# megacommand24.net
KiCad netlist of a schematic drawn in EAGLE
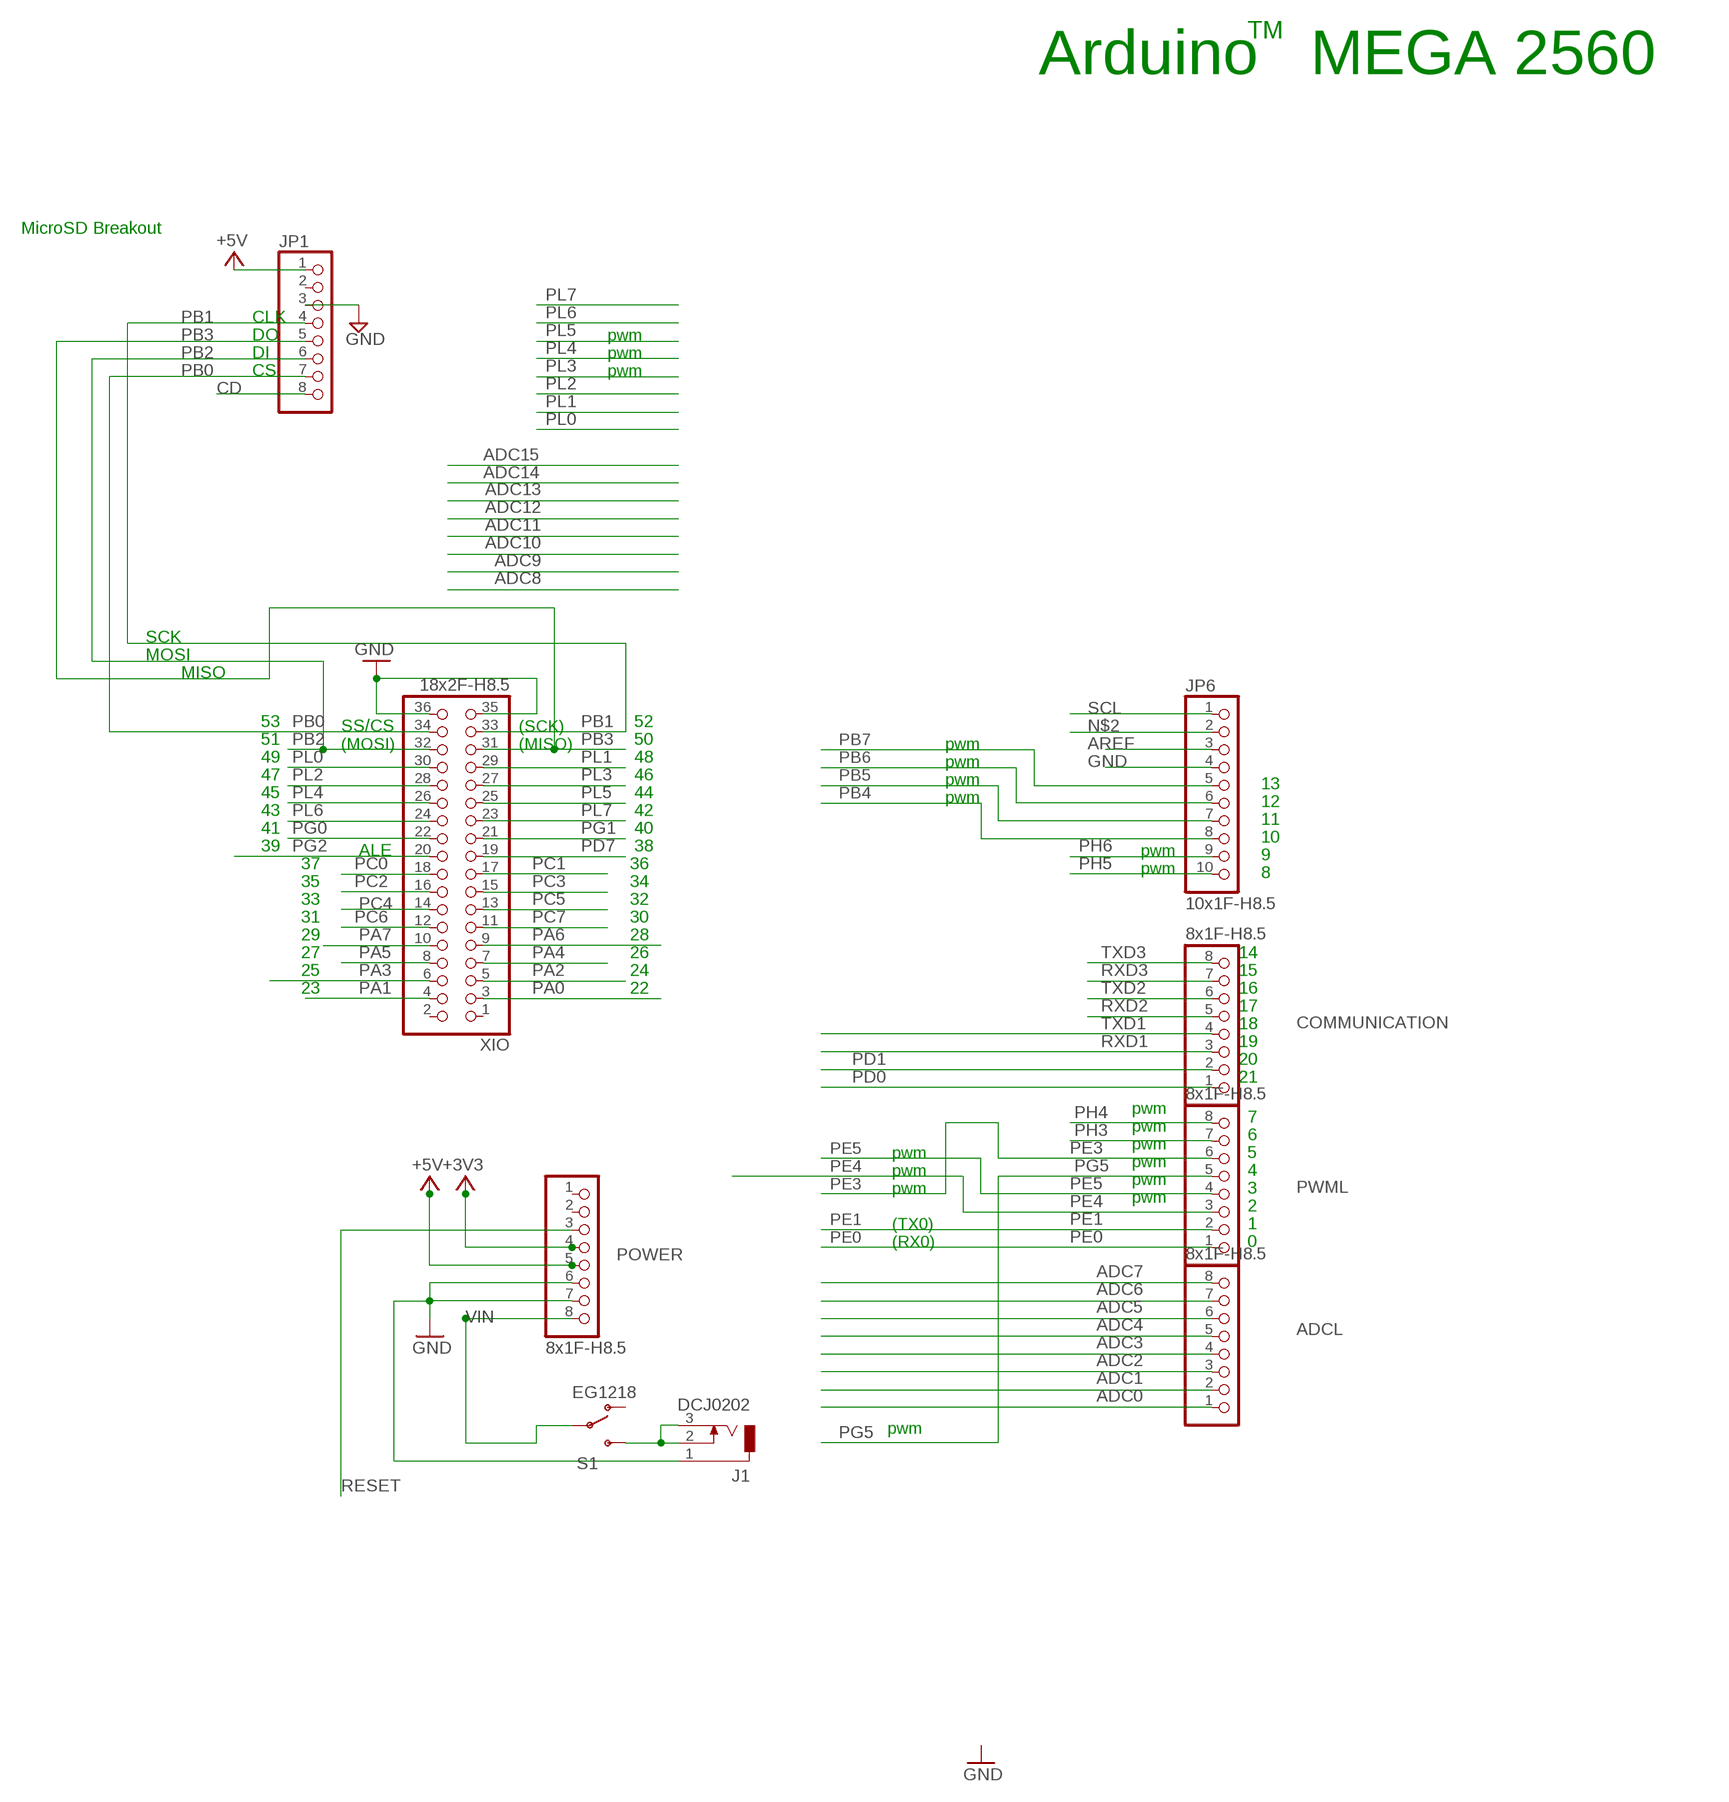
[diagram p0: schematic, sheet 1]
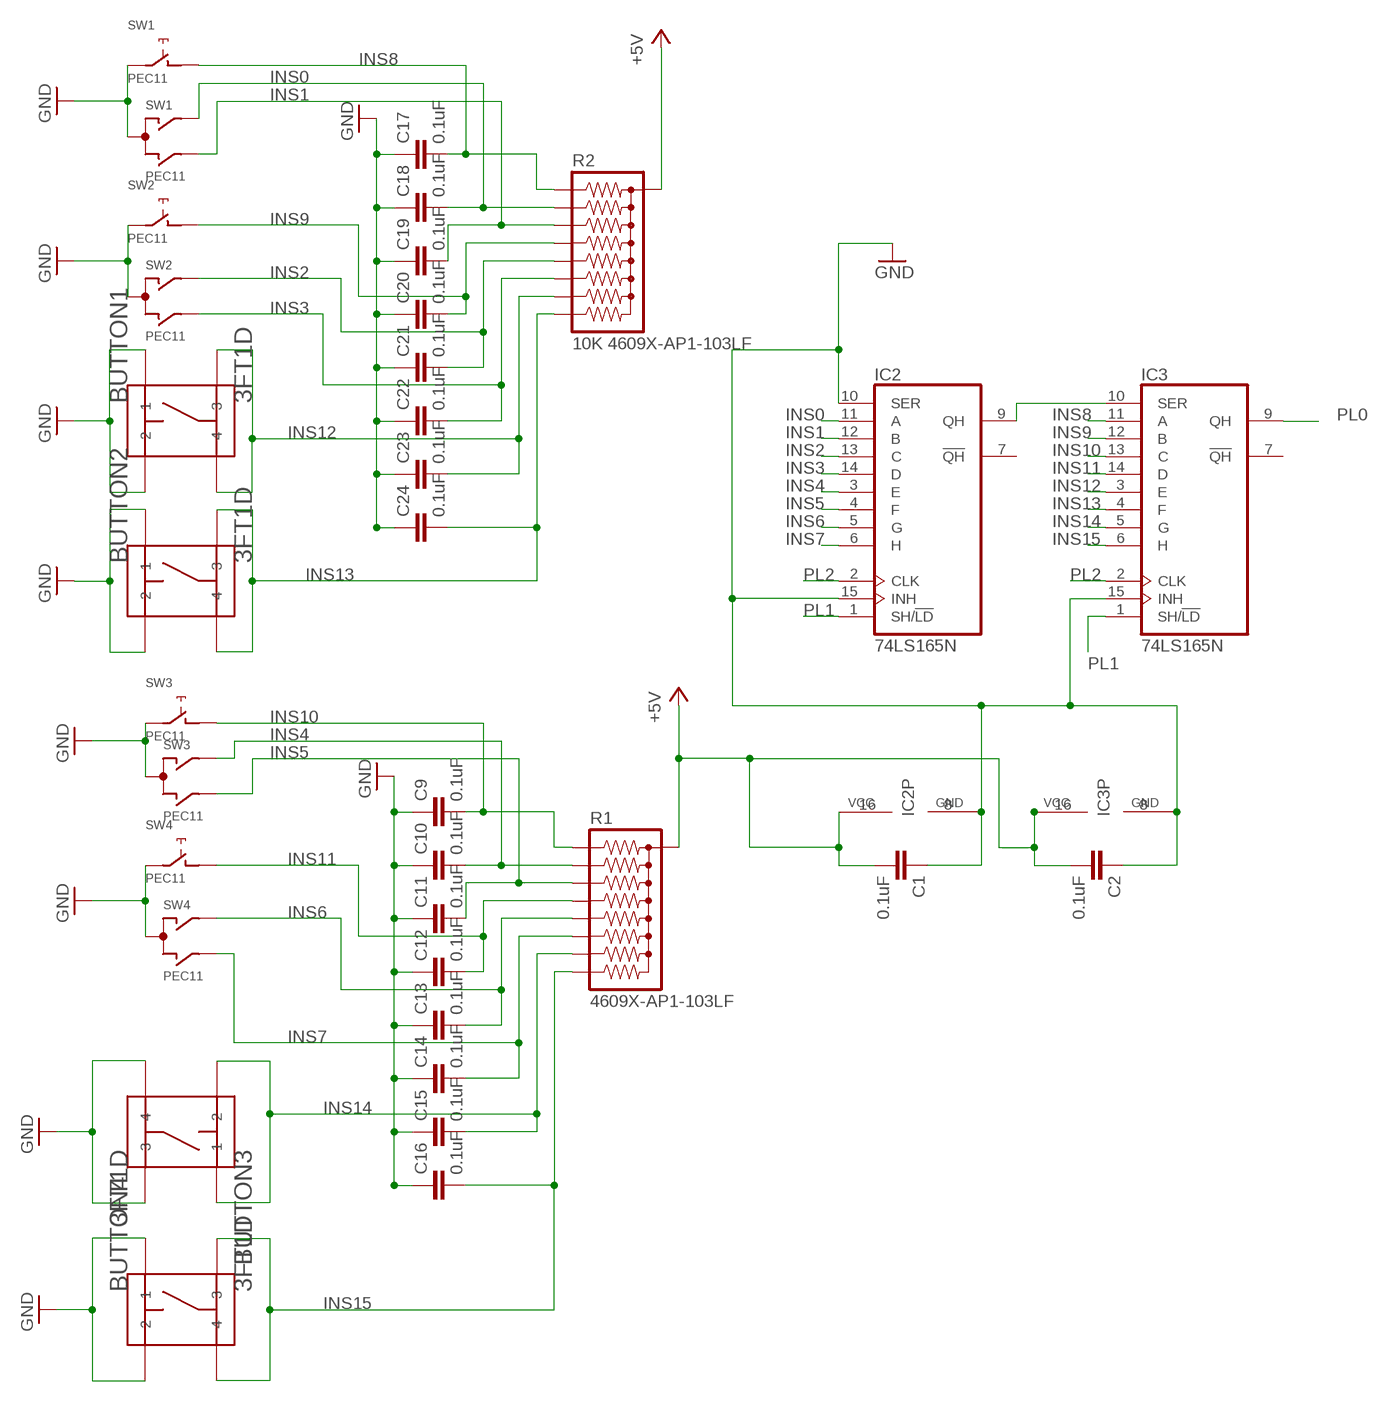
[diagram p1: schematic, sheet 2]
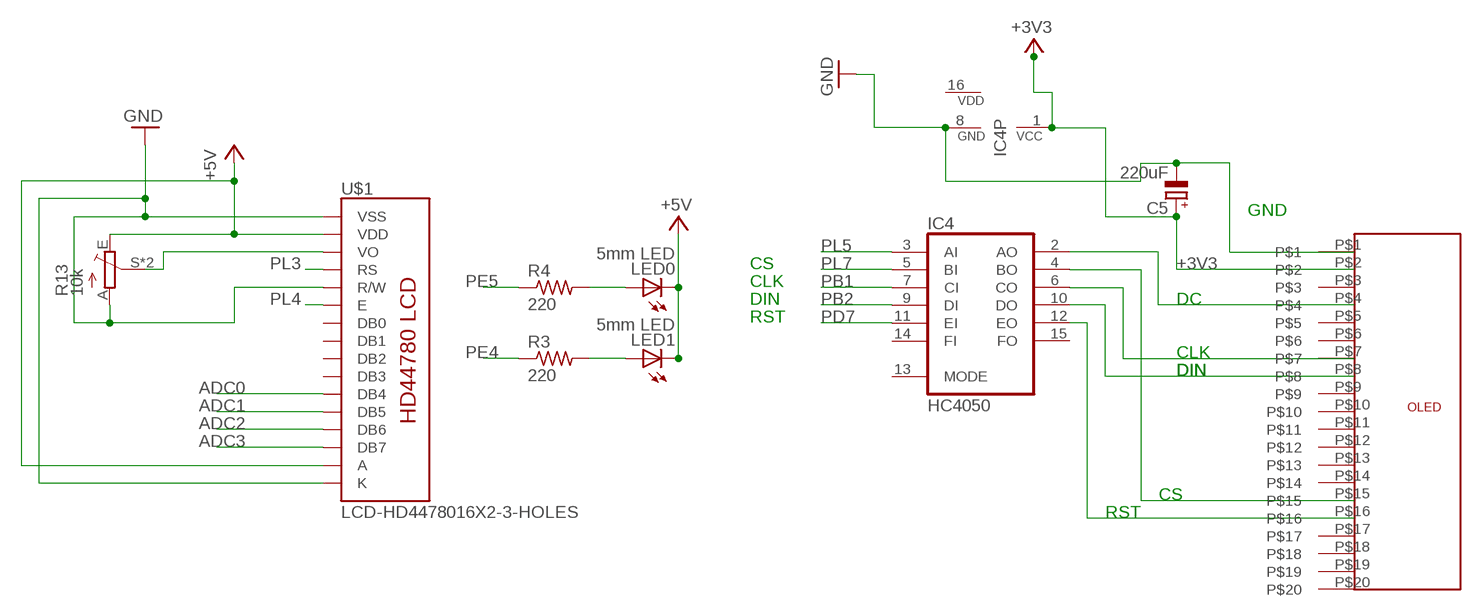
[diagram p2: schematic, sheet 3]
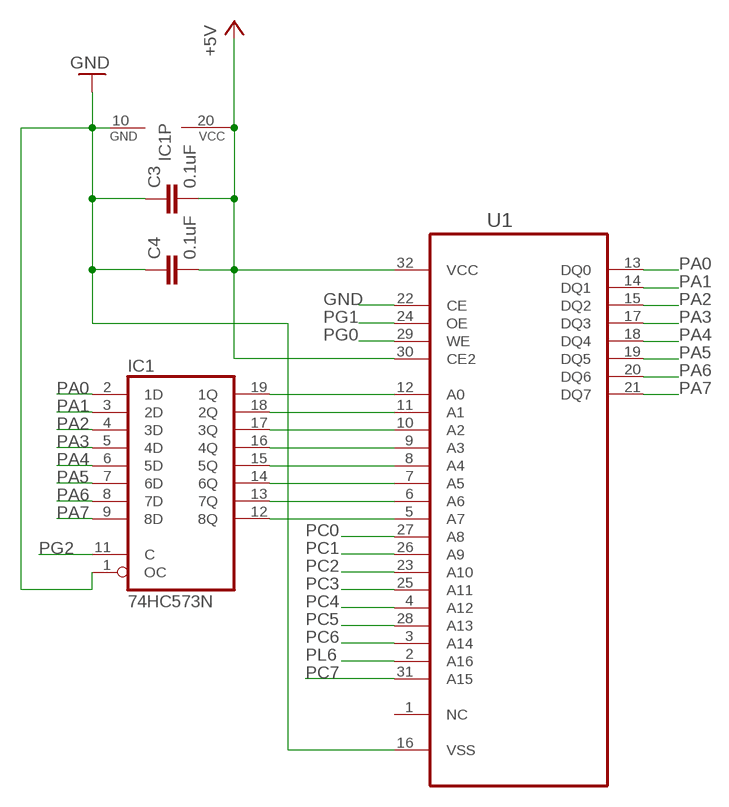
[diagram p3: schematic, sheet 4]
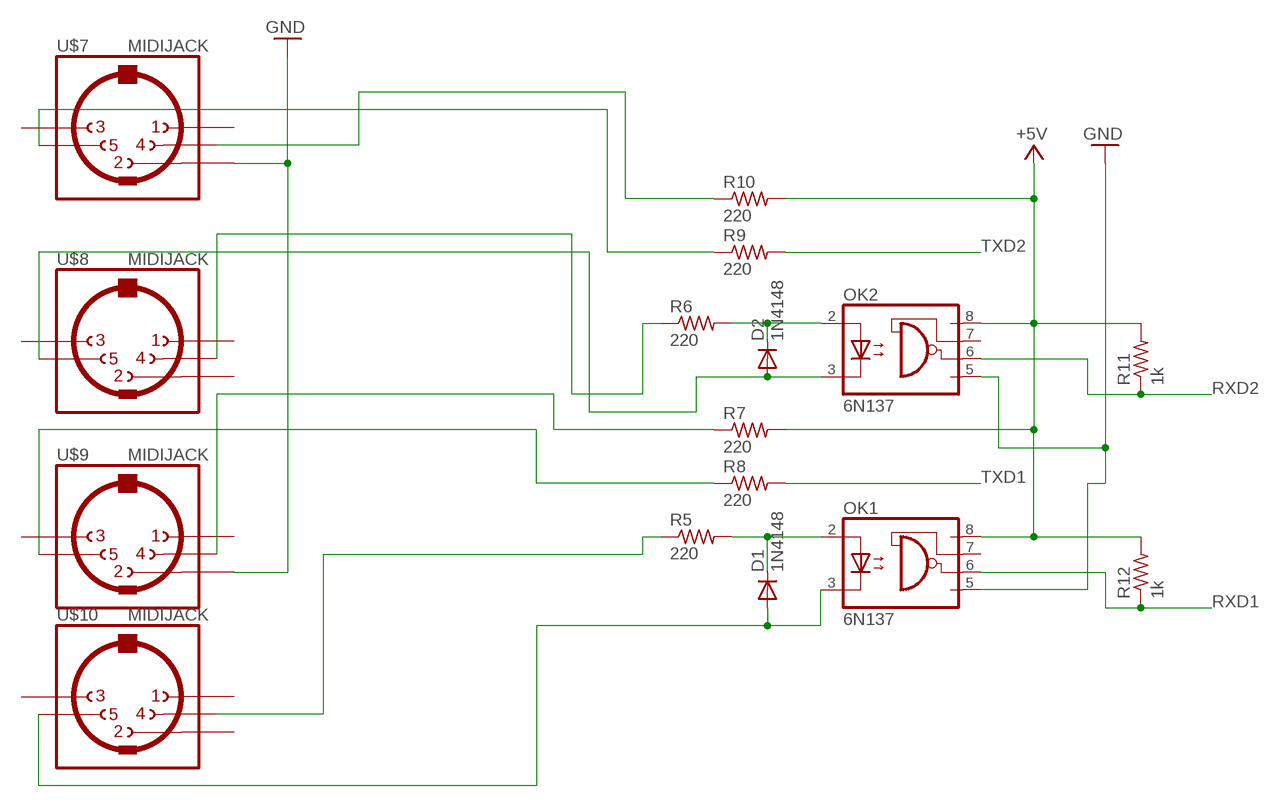
[diagram p4: schematic, sheet 5]

(export (version "E")
  (design (tool "Eeschema 10.0.6"))
  (components
    (comp (ref "ADCL")
      (value "8x1F-H8.5")
      (footprint "eagle-import:1X08")
      (libsource (lib "eagle-import") (part "PINHD-1X8"))
    )
    (comp (ref "COMMUNICATION")
      (value "8x1F-H8.5")
      (footprint "eagle-import:1X08")
      (libsource (lib "eagle-import") (part "PINHD-1X8"))
    )
    (comp (ref "J1")
      (value "DCJ0202")
      (footprint "eagle-import:DCJ0202")
      (libsource (lib "eagle-import") (part "DCJ0202"))
    )
    (comp (ref "JP1")
      (value "PINHD-1X8BIG")
      (footprint "eagle-import:1X08-BIG")
      (libsource (lib "eagle-import") (part "PINHD-1X8BIG"))
    )
    (comp (ref "JP6")
      (value "10x1F-H8.5")
      (footprint "eagle-import:1X10")
      (libsource (lib "eagle-import") (part "PINHD-1X10_ARD"))
    )
    (comp (ref "POWER")
      (value "8x1F-H8.5")
      (footprint "eagle-import:1X08")
      (libsource (lib "eagle-import") (part "PINHD-1X8"))
    )
    (comp (ref "PWML")
      (value "8x1F-H8.5")
      (footprint "eagle-import:1X08")
      (libsource (lib "eagle-import") (part "PINHD-1X8"))
    )
    (comp (ref "S1")
      (value "EG1218")
      (footprint "eagle-import:SWITCH-SPDT_KIT")
      (libsource (lib "eagle-import") (part "SWITCH-SPDTKIT"))
    )
    (comp (ref "XIO")
      (value "18x2F-H8.5")
      (footprint "eagle-import:2X18")
      (libsource (lib "eagle-import") (part "PINHD-2X18"))
    )
    (comp (ref "D1")
      (value "1N4148")
      (footprint "eagle-import:DO35-7")
      (libsource (lib "eagle-import") (part "1N4148DO35-7"))
    )
    (comp (ref "D2")
      (value "1N4148")
      (footprint "eagle-import:DO35-7")
      (libsource (lib "eagle-import") (part "1N4148DO35-7"))
    )
    (comp (ref "OK1")
      (value "6N137")
      (footprint "eagle-import:DIL08")
      (libsource (lib "eagle-import") (part "6N137"))
    )
    (comp (ref "OK2")
      (value "6N137")
      (footprint "eagle-import:DIL08")
      (libsource (lib "eagle-import") (part "6N137"))
    )
    (comp (ref "R5")
      (value "220")
      (footprint "eagle-import:0207_7")
      (libsource (lib "eagle-import") (part "R-US_0207/7"))
    )
    (comp (ref "R6")
      (value "220")
      (footprint "eagle-import:0207_7")
      (libsource (lib "eagle-import") (part "R-US_0207/7"))
    )
    (comp (ref "R7")
      (value "220")
      (footprint "eagle-import:0207_7")
      (libsource (lib "eagle-import") (part "R-US_0207/7"))
    )
    (comp (ref "R8")
      (value "220")
      (footprint "eagle-import:0207_7")
      (libsource (lib "eagle-import") (part "R-US_0207/7"))
    )
    (comp (ref "R9")
      (value "220")
      (footprint "eagle-import:0207_7")
      (libsource (lib "eagle-import") (part "R-US_0207/7"))
    )
    (comp (ref "R10")
      (value "220")
      (footprint "eagle-import:0207_7")
      (libsource (lib "eagle-import") (part "R-US_0207/7"))
    )
    (comp (ref "R11")
      (value "1k")
      (footprint "eagle-import:0207_7")
      (libsource (lib "eagle-import") (part "R-US_0207/7"))
    )
    (comp (ref "R12")
      (value "1k")
      (footprint "eagle-import:0207_7")
      (libsource (lib "eagle-import") (part "R-US_0207/7"))
    )
    (comp (ref "U$7")
      (value "MIDIJACK")
      (footprint "eagle-import:CP-2350")
      (libsource (lib "eagle-import") (part "MIDIJACK"))
    )
    (comp (ref "U$8")
      (value "MIDIJACK")
      (footprint "eagle-import:CP-2350")
      (libsource (lib "eagle-import") (part "MIDIJACK"))
    )
    (comp (ref "U$9")
      (value "MIDIJACK")
      (footprint "eagle-import:CP-2350")
      (libsource (lib "eagle-import") (part "MIDIJACK"))
    )
    (comp (ref "U$10")
      (value "MIDIJACK")
      (footprint "eagle-import:CP-2350")
      (libsource (lib "eagle-import") (part "MIDIJACK"))
    )
    (comp (ref "C5")
      (value "220uF")
      (footprint "eagle-import:TT2D6")
      (libsource (lib "eagle-import") (part "CPOL-EUTT2D6"))
    )
    (comp (ref "IC4")
      (value "HC4050")
      (footprint "eagle-import:DIL16")
      (libsource (lib "eagle-import") (part "4504N"))
    )
    (comp (ref "LED0")
      (value "5mm LED")
      (footprint "eagle-import:LED_LD260")
      (libsource (lib "eagle-import") (part "LED_ELD260"))
    )
    (comp (ref "LED1")
      (value "5mm LED")
      (footprint "eagle-import:LED_LD260")
      (libsource (lib "eagle-import") (part "LED_ELD260"))
    )
    (comp (ref "R3")
      (value "220")
      (footprint "eagle-import:0207_7")
      (libsource (lib "eagle-import") (part "R-US_0207/7"))
    )
    (comp (ref "R4")
      (value "220")
      (footprint "eagle-import:0207_7")
      (libsource (lib "eagle-import") (part "R-US_0207/7"))
    )
    (comp (ref "R13")
      (value "10k")
      (footprint "eagle-import:CA6V")
      (libsource (lib "eagle-import") (part "TRIM_EU-CA6V"))
    )
    (comp (ref "U$1")
      (value "LCD-HD4478016X2-3-HOLES")
      (footprint "eagle-import:LCD-16X2-3HOLES")
      (libsource (lib "eagle-import") (part "LCD-HD4478016X2-3-HOLES"))
    )
    (comp (ref "U$2")
      (value "20PIN")
      (footprint "eagle-import:20PIN")
      (libsource (lib "eagle-import") (part "20PIN"))
    )
    (comp (ref "BUTTON1")
      (value "3FT1D")
      (footprint "eagle-import:3FT")
      (libsource (lib "eagle-import") (part "3FT1D"))
    )
    (comp (ref "BUTTON2")
      (value "3FT1D")
      (footprint "eagle-import:3FT")
      (libsource (lib "eagle-import") (part "3FT1D"))
    )
    (comp (ref "BUTTON3")
      (value "3FT1D")
      (footprint "eagle-import:3FT")
      (libsource (lib "eagle-import") (part "3FT1D"))
    )
    (comp (ref "BUTTON4")
      (value "3FT1D")
      (footprint "eagle-import:3FT")
      (libsource (lib "eagle-import") (part "3FT1D"))
    )
    (comp (ref "C1")
      (value "0.1uF")
      (footprint "eagle-import:C025-050X050")
      (libsource (lib "eagle-import") (part "C-EU025-050X050"))
    )
    (comp (ref "C2")
      (value "0.1uF")
      (footprint "eagle-import:C025-050X050")
      (libsource (lib "eagle-import") (part "C-EU025-050X050"))
    )
    (comp (ref "C9")
      (value "0.1uF")
      (footprint "eagle-import:C025-050X050")
      (libsource (lib "eagle-import") (part "C-EU025-050X050"))
    )
    (comp (ref "C10")
      (value "0.1uF")
      (footprint "eagle-import:C025-050X050")
      (libsource (lib "eagle-import") (part "C-EU025-050X050"))
    )
    (comp (ref "C11")
      (value "0.1uF")
      (footprint "eagle-import:C025-050X050")
      (libsource (lib "eagle-import") (part "C-EU025-050X050"))
    )
    (comp (ref "C12")
      (value "0.1uF")
      (footprint "eagle-import:C025-050X050")
      (libsource (lib "eagle-import") (part "C-EU025-050X050"))
    )
    (comp (ref "C13")
      (value "0.1uF")
      (footprint "eagle-import:C025-050X050")
      (libsource (lib "eagle-import") (part "C-EU025-050X050"))
    )
    (comp (ref "C14")
      (value "0.1uF")
      (footprint "eagle-import:C025-050X050")
      (libsource (lib "eagle-import") (part "C-EU025-050X050"))
    )
    (comp (ref "C15")
      (value "0.1uF")
      (footprint "eagle-import:C025-050X050")
      (libsource (lib "eagle-import") (part "C-EU025-050X050"))
    )
    (comp (ref "C16")
      (value "0.1uF")
      (footprint "eagle-import:C025-050X050")
      (libsource (lib "eagle-import") (part "C-EU025-050X050"))
    )
    (comp (ref "C17")
      (value "0.1uF")
      (footprint "eagle-import:C025-050X050")
      (libsource (lib "eagle-import") (part "C-EU025-050X050"))
    )
    (comp (ref "C18")
      (value "0.1uF")
      (footprint "eagle-import:C025-050X050")
      (libsource (lib "eagle-import") (part "C-EU025-050X050"))
    )
    (comp (ref "C19")
      (value "0.1uF")
      (footprint "eagle-import:C025-050X050")
      (libsource (lib "eagle-import") (part "C-EU025-050X050"))
    )
    (comp (ref "C20")
      (value "0.1uF")
      (footprint "eagle-import:C025-050X050")
      (libsource (lib "eagle-import") (part "C-EU025-050X050"))
    )
    (comp (ref "C21")
      (value "0.1uF")
      (footprint "eagle-import:C025-050X050")
      (libsource (lib "eagle-import") (part "C-EU025-050X050"))
    )
    (comp (ref "C22")
      (value "0.1uF")
      (footprint "eagle-import:C025-050X050")
      (libsource (lib "eagle-import") (part "C-EU025-050X050"))
    )
    (comp (ref "C23")
      (value "0.1uF")
      (footprint "eagle-import:C025-050X050")
      (libsource (lib "eagle-import") (part "C-EU025-050X050"))
    )
    (comp (ref "C24")
      (value "0.1uF")
      (footprint "eagle-import:C025-050X050")
      (libsource (lib "eagle-import") (part "C-EU025-050X050"))
    )
    (comp (ref "IC2")
      (value "74LS165N")
      (footprint "eagle-import:DIL16")
      (libsource (lib "eagle-import") (part "74165NLS"))
    )
    (comp (ref "IC3")
      (value "74LS165N")
      (footprint "eagle-import:DIL16")
      (libsource (lib "eagle-import") (part "74165NLS"))
    )
    (comp (ref "R1")
      (value "4609X-AP1-103LF")
      (footprint "eagle-import:RPACK-SIP-PTH-8")
      (libsource (lib "eagle-import") (part "RPACK-BUSSED-8-SIP-PTH-8"))
    )
    (comp (ref "R2")
      (value "10K 4609X-AP1-103LF")
      (footprint "eagle-import:RPACK-SIP-PTH-8")
      (libsource (lib "eagle-import") (part "RPACK-BUSSED-8-SIP-PTH-8"))
    )
    (comp (ref "SW1")
      (value "PEC11")
      (footprint "eagle-import:ALPS_EC12E_SW")
      (fields (field (name "MPN") "EC12E2424407"))
      (libsource (lib "eagle-import") (part "EC12E_SW"))
    )
    (comp (ref "SW2")
      (value "PEC11")
      (footprint "eagle-import:ALPS_EC12E_SW")
      (fields (field (name "MPN") "EC12E2424407"))
      (libsource (lib "eagle-import") (part "EC12E_SW"))
    )
    (comp (ref "SW3")
      (value "PEC11")
      (footprint "eagle-import:ALPS_EC12E_SW")
      (fields (field (name "MPN") "EC12E2424407"))
      (libsource (lib "eagle-import") (part "EC12E_SW"))
    )
    (comp (ref "SW4")
      (value "PEC11")
      (footprint "eagle-import:ALPS_EC12E_SW")
      (fields (field (name "MPN") "EC12E2424407"))
      (libsource (lib "eagle-import") (part "EC12E_SW"))
    )
    (comp (ref "C3")
      (value "0.1uF")
      (footprint "eagle-import:C025-050X050")
      (libsource (lib "eagle-import") (part "C-EU025-050X050"))
    )
    (comp (ref "C4")
      (value "0.1uF")
      (footprint "eagle-import:C025-050X050")
      (libsource (lib "eagle-import") (part "C-EU025-050X050"))
    )
    (comp (ref "IC1")
      (value "74HC573N")
      (footprint "eagle-import:DIL20")
      (libsource (lib "eagle-import") (part "74573NHC"))
    )
    (comp (ref "U1")
      (value "AS6C1008-55PCN")
      (footprint "eagle-import:DIP254P1524X393-32")
      (libsource (lib "eagle-import") (part "AS6C1008-55PCN"))
    )
  )
  (nets
    (net (code "1") (name "+3V3") (class "Default")
      (node (ref "C5") (pin "+") (pinfunction "+_+") (pintype "passive"))
      (node (ref "IC4") (pin "1") (pinfunction "VCC_1") (pintype "power_in"))
      (node (ref "POWER") (pin "4") (pinfunction "4_4") (pintype "passive"))
      (node (ref "U$2") (pin "P$2") (pinfunction "P$2_P$2") (pintype "bidirectional"))
    )
    (net (code "2") (name "+5V") (class "Default")
      (node (ref "C1") (pin "2") (pinfunction "2_2") (pintype "passive"))
      (node (ref "C2") (pin "2") (pinfunction "2_2") (pintype "passive"))
      (node (ref "C3") (pin "2") (pinfunction "2_2") (pintype "passive"))
      (node (ref "C4") (pin "2") (pinfunction "2_2") (pintype "passive"))
      (node (ref "IC1") (pin "20") (pinfunction "VCC_20") (pintype "power_in"))
      (node (ref "IC2") (pin "16") (pinfunction "VCC_16") (pintype "power_in"))
      (node (ref "IC3") (pin "16") (pinfunction "VCC_16") (pintype "power_in"))
      (node (ref "JP1") (pin "1") (pinfunction "1_1") (pintype "passive"))
      (node (ref "LED0") (pin "K") (pinfunction "C_K") (pintype "passive"))
      (node (ref "LED1") (pin "K") (pinfunction "C_K") (pintype "passive"))
      (node (ref "OK1") (pin "8") (pinfunction "VCC_8") (pintype "passive"))
      (node (ref "OK2") (pin "8") (pinfunction "VCC_8") (pintype "passive"))
      (node (ref "POWER") (pin "5") (pinfunction "5_5") (pintype "passive"))
      (node (ref "R1") (pin "P$1") (pinfunction "1_P$1") (pintype "passive"))
      (node (ref "R10") (pin "2") (pinfunction "2_2") (pintype "passive"))
      (node (ref "R11") (pin "2") (pinfunction "2_2") (pintype "passive"))
      (node (ref "R12") (pin "2") (pinfunction "2_2") (pintype "passive"))
      (node (ref "R13") (pin "E") (pinfunction "E_E") (pintype "passive"))
      (node (ref "R2") (pin "P$1") (pinfunction "1_P$1") (pintype "passive"))
      (node (ref "R7") (pin "2") (pinfunction "2_2") (pintype "passive"))
      (node (ref "U$1") (pin "15") (pinfunction "A_15") (pintype "power_in"))
      (node (ref "U$1") (pin "2") (pinfunction "VDD_2") (pintype "power_in"))
      (node (ref "U1") (pin "30") (pinfunction "CE2_30") (pintype "input"))
      (node (ref "U1") (pin "32") (pinfunction "VCC_32") (pintype "power_in"))
    )
    (net (code "3") (name "ADC0") (class "Default")
      (node (ref "ADCL") (pin "1") (pinfunction "1_1") (pintype "passive"))
      (node (ref "U$1") (pin "11") (pinfunction "DB4_11") (pintype "bidirectional"))
    )
    (net (code "4") (name "ADC1") (class "Default")
      (node (ref "ADCL") (pin "2") (pinfunction "2_2") (pintype "passive"))
      (node (ref "U$1") (pin "12") (pinfunction "DB5_12") (pintype "bidirectional"))
    )
    (net (code "5") (name "ADC2") (class "Default")
      (node (ref "ADCL") (pin "3") (pinfunction "3_3") (pintype "passive"))
      (node (ref "U$1") (pin "13") (pinfunction "DB6_13") (pintype "bidirectional"))
    )
    (net (code "6") (name "ADC3") (class "Default")
      (node (ref "ADCL") (pin "4") (pinfunction "4_4") (pintype "passive"))
      (node (ref "U$1") (pin "14") (pinfunction "DB7_14") (pintype "bidirectional"))
    )
    (net (code "7") (name "ADC4") (class "Default")
      (node (ref "ADCL") (pin "5") (pinfunction "5_5") (pintype "passive"))
    )
    (net (code "8") (name "ADC5") (class "Default")
      (node (ref "ADCL") (pin "6") (pinfunction "6_6") (pintype "passive"))
    )
    (net (code "9") (name "ADC6") (class "Default")
      (node (ref "ADCL") (pin "7") (pinfunction "7_7") (pintype "passive"))
    )
    (net (code "10") (name "ADC7") (class "Default")
      (node (ref "ADCL") (pin "8") (pinfunction "8_8") (pintype "passive"))
    )
    (net (code "19") (name "AREF") (class "Default")
      (node (ref "JP6") (pin "3") (pinfunction "3_3") (pintype "passive"))
    )
    (net (code "20") (name "CD") (class "Default")
      (node (ref "JP1") (pin "8") (pinfunction "8_8") (pintype "passive"))
    )
    (net (code "21") (name "GND") (class "Default")
      (node (ref "BUTTON1") (pin "P$1") (pinfunction "1_P$1") (pintype "bidirectional"))
      (node (ref "BUTTON1") (pin "P$2") (pinfunction "2_P$2") (pintype "bidirectional"))
      (node (ref "BUTTON2") (pin "P$1") (pinfunction "1_P$1") (pintype "bidirectional"))
      (node (ref "BUTTON2") (pin "P$2") (pinfunction "2_P$2") (pintype "bidirectional"))
      (node (ref "BUTTON3") (pin "P$3") (pinfunction "3_P$3") (pintype "bidirectional"))
      (node (ref "BUTTON3") (pin "P$4") (pinfunction "4_P$4") (pintype "bidirectional"))
      (node (ref "BUTTON4") (pin "P$1") (pinfunction "1_P$1") (pintype "bidirectional"))
      (node (ref "BUTTON4") (pin "P$2") (pinfunction "2_P$2") (pintype "bidirectional"))
      (node (ref "C1") (pin "1") (pinfunction "1_1") (pintype "passive"))
      (node (ref "C10") (pin "1") (pinfunction "1_1") (pintype "passive"))
      (node (ref "C11") (pin "1") (pinfunction "1_1") (pintype "passive"))
      (node (ref "C12") (pin "1") (pinfunction "1_1") (pintype "passive"))
      (node (ref "C13") (pin "1") (pinfunction "1_1") (pintype "passive"))
      (node (ref "C14") (pin "1") (pinfunction "1_1") (pintype "passive"))
      (node (ref "C15") (pin "1") (pinfunction "1_1") (pintype "passive"))
      (node (ref "C16") (pin "1") (pinfunction "1_1") (pintype "passive"))
      (node (ref "C17") (pin "1") (pinfunction "1_1") (pintype "passive"))
      (node (ref "C18") (pin "1") (pinfunction "1_1") (pintype "passive"))
      (node (ref "C19") (pin "1") (pinfunction "1_1") (pintype "passive"))
      (node (ref "C2") (pin "1") (pinfunction "1_1") (pintype "passive"))
      (node (ref "C20") (pin "1") (pinfunction "1_1") (pintype "passive"))
      (node (ref "C21") (pin "1") (pinfunction "1_1") (pintype "passive"))
      (node (ref "C22") (pin "1") (pinfunction "1_1") (pintype "passive"))
      (node (ref "C23") (pin "1") (pinfunction "1_1") (pintype "passive"))
      (node (ref "C24") (pin "1") (pinfunction "1_1") (pintype "passive"))
      (node (ref "C3") (pin "1") (pinfunction "1_1") (pintype "passive"))
      (node (ref "C4") (pin "1") (pinfunction "1_1") (pintype "passive"))
      (node (ref "C5") (pin "-") (pinfunction "-_-") (pintype "passive"))
      (node (ref "C9") (pin "1") (pinfunction "1_1") (pintype "passive"))
      (node (ref "IC1") (pin "1") (pinfunction "OC_1") (pintype "input"))
      (node (ref "IC1") (pin "10") (pinfunction "GND_10") (pintype "power_in"))
      (node (ref "IC2") (pin "10") (pinfunction "SER_10") (pintype "input"))
      (node (ref "IC2") (pin "15") (pinfunction "INH_15") (pintype "input"))
      (node (ref "IC2") (pin "8") (pinfunction "GND_8") (pintype "power_in"))
      (node (ref "IC3") (pin "15") (pinfunction "INH_15") (pintype "input"))
      (node (ref "IC3") (pin "8") (pinfunction "GND_8") (pintype "power_in"))
      (node (ref "IC4") (pin "8") (pinfunction "GND_8") (pintype "power_in"))
      (node (ref "J1") (pin "1") (pinfunction "1_1") (pintype "passive"))
      (node (ref "JP1") (pin "3") (pinfunction "3_3") (pintype "passive"))
      (node (ref "JP6") (pin "4") (pinfunction "4_4") (pintype "passive"))
      (node (ref "OK1") (pin "5") (pinfunction "GND_5") (pintype "passive"))
      (node (ref "OK2") (pin "5") (pinfunction "GND_5") (pintype "passive"))
      (node (ref "POWER") (pin "6") (pinfunction "6_6") (pintype "passive"))
      (node (ref "POWER") (pin "7") (pinfunction "7_7") (pintype "passive"))
      (node (ref "R13") (pin "A") (pinfunction "A_A") (pintype "passive"))
      (node (ref "SW1") (pin "C") (pinfunction "C_C") (pintype "passive"))
      (node (ref "SW1") (pin "E") (pinfunction "2_E") (pintype "passive"))
      (node (ref "SW2") (pin "C") (pinfunction "C_C") (pintype "passive"))
      (node (ref "SW2") (pin "E") (pinfunction "2_E") (pintype "passive"))
      (node (ref "SW3") (pin "C") (pinfunction "C_C") (pintype "passive"))
      (node (ref "SW3") (pin "E") (pinfunction "2_E") (pintype "passive"))
      (node (ref "SW4") (pin "C") (pinfunction "C_C") (pintype "passive"))
      (node (ref "SW4") (pin "E") (pinfunction "2_E") (pintype "passive"))
      (node (ref "U$1") (pin "1") (pinfunction "VSS_1") (pintype "power_in"))
      (node (ref "U$1") (pin "16") (pinfunction "K_16") (pintype "power_in"))
      (node (ref "U$1") (pin "5") (pinfunction "R/W_5") (pintype "input"))
      (node (ref "U$2") (pin "P$1") (pinfunction "P$1_P$1") (pintype "bidirectional"))
      (node (ref "U$7") (pin "2") (pinfunction "2_2") (pintype "passive"))
      (node (ref "U$9") (pin "2") (pinfunction "2_2") (pintype "passive"))
      (node (ref "U1") (pin "16") (pinfunction "VSS_16") (pintype "bidirectional"))
      (node (ref "U1") (pin "22") (pinfunction "CE_22") (pintype "input"))
      (node (ref "XIO") (pin "35") (pinfunction "35_35") (pintype "passive"))
      (node (ref "XIO") (pin "36") (pinfunction "36_36") (pintype "passive"))
    )
    (net (code "22") (name "INS0") (class "Default")
      (node (ref "C18") (pin "2") (pinfunction "2_2") (pintype "passive"))
      (node (ref "IC2") (pin "11") (pinfunction "A_11") (pintype "input"))
      (node (ref "R2") (pin "P$3") (pinfunction "3_P$3") (pintype "passive"))
      (node (ref "SW1") (pin "A") (pinfunction "A_A") (pintype "passive"))
    )
    (net (code "23") (name "INS1") (class "Default")
      (node (ref "C19") (pin "2") (pinfunction "2_2") (pintype "passive"))
      (node (ref "IC2") (pin "12") (pinfunction "B_12") (pintype "input"))
      (node (ref "R2") (pin "P$4") (pinfunction "4_P$4") (pintype "passive"))
      (node (ref "SW1") (pin "B") (pinfunction "B_B") (pintype "passive"))
    )
    (net (code "24") (name "INS2") (class "Default")
      (node (ref "C21") (pin "2") (pinfunction "2_2") (pintype "passive"))
      (node (ref "IC2") (pin "13") (pinfunction "C_13") (pintype "input"))
      (node (ref "R2") (pin "P$6") (pinfunction "6_P$6") (pintype "passive"))
      (node (ref "SW2") (pin "A") (pinfunction "A_A") (pintype "passive"))
    )
    (net (code "25") (name "INS3") (class "Default")
      (node (ref "C22") (pin "2") (pinfunction "2_2") (pintype "passive"))
      (node (ref "IC2") (pin "14") (pinfunction "D_14") (pintype "input"))
      (node (ref "R2") (pin "P$7") (pinfunction "7_P$7") (pintype "passive"))
      (node (ref "SW2") (pin "B") (pinfunction "B_B") (pintype "passive"))
    )
    (net (code "26") (name "INS4") (class "Default")
      (node (ref "C10") (pin "2") (pinfunction "2_2") (pintype "passive"))
      (node (ref "IC2") (pin "3") (pinfunction "E_3") (pintype "input"))
      (node (ref "R1") (pin "P$3") (pinfunction "3_P$3") (pintype "passive"))
      (node (ref "SW3") (pin "A") (pinfunction "A_A") (pintype "passive"))
    )
    (net (code "27") (name "INS5") (class "Default")
      (node (ref "C11") (pin "2") (pinfunction "2_2") (pintype "passive"))
      (node (ref "IC2") (pin "4") (pinfunction "F_4") (pintype "input"))
      (node (ref "R1") (pin "P$4") (pinfunction "4_P$4") (pintype "passive"))
      (node (ref "SW3") (pin "B") (pinfunction "B_B") (pintype "passive"))
    )
    (net (code "28") (name "INS6") (class "Default")
      (node (ref "C13") (pin "2") (pinfunction "2_2") (pintype "passive"))
      (node (ref "IC2") (pin "5") (pinfunction "G_5") (pintype "input"))
      (node (ref "R1") (pin "P$6") (pinfunction "6_P$6") (pintype "passive"))
      (node (ref "SW4") (pin "A") (pinfunction "A_A") (pintype "passive"))
    )
    (net (code "29") (name "INS7") (class "Default")
      (node (ref "C14") (pin "2") (pinfunction "2_2") (pintype "passive"))
      (node (ref "IC2") (pin "6") (pinfunction "H_6") (pintype "input"))
      (node (ref "R1") (pin "P$7") (pinfunction "7_P$7") (pintype "passive"))
      (node (ref "SW4") (pin "B") (pinfunction "B_B") (pintype "passive"))
    )
    (net (code "30") (name "INS8") (class "Default")
      (node (ref "C17") (pin "2") (pinfunction "2_2") (pintype "passive"))
      (node (ref "IC3") (pin "11") (pinfunction "A_11") (pintype "input"))
      (node (ref "R2") (pin "P$2") (pinfunction "2_P$2") (pintype "passive"))
      (node (ref "SW1") (pin "D") (pinfunction "1_D") (pintype "passive"))
    )
    (net (code "31") (name "INS9") (class "Default")
      (node (ref "C20") (pin "2") (pinfunction "2_2") (pintype "passive"))
      (node (ref "IC3") (pin "12") (pinfunction "B_12") (pintype "input"))
      (node (ref "R2") (pin "P$5") (pinfunction "5_P$5") (pintype "passive"))
      (node (ref "SW2") (pin "D") (pinfunction "1_D") (pintype "passive"))
    )
    (net (code "32") (name "INS10") (class "Default")
      (node (ref "C9") (pin "2") (pinfunction "2_2") (pintype "passive"))
      (node (ref "IC3") (pin "13") (pinfunction "C_13") (pintype "input"))
      (node (ref "R1") (pin "P$2") (pinfunction "2_P$2") (pintype "passive"))
      (node (ref "SW3") (pin "D") (pinfunction "1_D") (pintype "passive"))
    )
    (net (code "33") (name "INS11") (class "Default")
      (node (ref "C12") (pin "2") (pinfunction "2_2") (pintype "passive"))
      (node (ref "IC3") (pin "14") (pinfunction "D_14") (pintype "input"))
      (node (ref "R1") (pin "P$5") (pinfunction "5_P$5") (pintype "passive"))
      (node (ref "SW4") (pin "D") (pinfunction "1_D") (pintype "passive"))
    )
    (net (code "34") (name "INS12") (class "Default")
      (node (ref "BUTTON1") (pin "P$3") (pinfunction "3_P$3") (pintype "bidirectional"))
      (node (ref "BUTTON1") (pin "P$4") (pinfunction "4_P$4") (pintype "bidirectional"))
      (node (ref "C23") (pin "2") (pinfunction "2_2") (pintype "passive"))
      (node (ref "IC3") (pin "3") (pinfunction "E_3") (pintype "input"))
      (node (ref "R2") (pin "P$8") (pinfunction "8_P$8") (pintype "passive"))
    )
    (net (code "35") (name "INS13") (class "Default")
      (node (ref "BUTTON2") (pin "P$3") (pinfunction "3_P$3") (pintype "bidirectional"))
      (node (ref "BUTTON2") (pin "P$4") (pinfunction "4_P$4") (pintype "bidirectional"))
      (node (ref "C24") (pin "2") (pinfunction "2_2") (pintype "passive"))
      (node (ref "IC3") (pin "4") (pinfunction "F_4") (pintype "input"))
      (node (ref "R2") (pin "P$9") (pinfunction "9_P$9") (pintype "passive"))
    )
    (net (code "36") (name "INS14") (class "Default")
      (node (ref "BUTTON3") (pin "P$1") (pinfunction "1_P$1") (pintype "bidirectional"))
      (node (ref "BUTTON3") (pin "P$2") (pinfunction "2_P$2") (pintype "bidirectional"))
      (node (ref "C15") (pin "2") (pinfunction "2_2") (pintype "passive"))
      (node (ref "IC3") (pin "5") (pinfunction "G_5") (pintype "input"))
      (node (ref "R1") (pin "P$8") (pinfunction "8_P$8") (pintype "passive"))
    )
    (net (code "37") (name "INS15") (class "Default")
      (node (ref "BUTTON4") (pin "P$3") (pinfunction "3_P$3") (pintype "bidirectional"))
      (node (ref "BUTTON4") (pin "P$4") (pinfunction "4_P$4") (pintype "bidirectional"))
      (node (ref "C16") (pin "2") (pinfunction "2_2") (pintype "passive"))
      (node (ref "IC3") (pin "6") (pinfunction "H_6") (pintype "input"))
      (node (ref "R1") (pin "P$9") (pinfunction "9_P$9") (pintype "passive"))
    )
    (net (code "38") (name "N$2") (class "Default")
      (node (ref "JP6") (pin "2") (pinfunction "2_2") (pintype "passive"))
    )
    (net (code "39") (name "Net-(IC1A-1Q)") (class "Default")
      (node (ref "IC1") (pin "19") (pinfunction "1Q_19") (pintype "tri_state"))
      (node (ref "U1") (pin "12") (pinfunction "A0_12") (pintype "input"))
    )
    (net (code "40") (name "Net-(IC1A-2Q)") (class "Default")
      (node (ref "IC1") (pin "18") (pinfunction "2Q_18") (pintype "tri_state"))
      (node (ref "U1") (pin "11") (pinfunction "A1_11") (pintype "input"))
    )
    (net (code "41") (name "Net-(IC1A-3Q)") (class "Default")
      (node (ref "IC1") (pin "17") (pinfunction "3Q_17") (pintype "tri_state"))
      (node (ref "U1") (pin "10") (pinfunction "A2_10") (pintype "input"))
    )
    (net (code "42") (name "Net-(IC1A-4Q)") (class "Default")
      (node (ref "IC1") (pin "16") (pinfunction "4Q_16") (pintype "tri_state"))
      (node (ref "U1") (pin "9") (pinfunction "A3_9") (pintype "input"))
    )
    (net (code "43") (name "Net-(IC1A-5Q)") (class "Default")
      (node (ref "IC1") (pin "15") (pinfunction "5Q_15") (pintype "tri_state"))
      (node (ref "U1") (pin "8") (pinfunction "A4_8") (pintype "input"))
    )
    (net (code "44") (name "Net-(IC1A-6Q)") (class "Default")
      (node (ref "IC1") (pin "14") (pinfunction "6Q_14") (pintype "tri_state"))
      (node (ref "U1") (pin "7") (pinfunction "A5_7") (pintype "input"))
    )
    (net (code "45") (name "Net-(IC1A-7Q)") (class "Default")
      (node (ref "IC1") (pin "13") (pinfunction "7Q_13") (pintype "tri_state"))
      (node (ref "U1") (pin "6") (pinfunction "A6_6") (pintype "input"))
    )
    (net (code "46") (name "Net-(IC1A-8Q)") (class "Default")
      (node (ref "IC1") (pin "12") (pinfunction "8Q_12") (pintype "tri_state"))
      (node (ref "U1") (pin "5") (pinfunction "A7_5") (pintype "input"))
    )
    (net (code "47") (name "Net-(IC2A-QH)") (class "Default")
      (node (ref "IC2") (pin "9") (pinfunction "QH_9") (pintype "output"))
      (node (ref "IC3") (pin "10") (pinfunction "SER_10") (pintype "input"))
    )
    (net (code "48") (name "Net-(IC4A-AO)") (class "Default")
      (node (ref "IC4") (pin "2") (pinfunction "AO_2") (pintype "output"))
      (node (ref "U$2") (pin "P$4") (pinfunction "P$4_P$4") (pintype "bidirectional"))
    )
    (net (code "49") (name "Net-(IC4A-BO)") (class "Default")
      (node (ref "IC4") (pin "4") (pinfunction "BO_4") (pintype "output"))
      (node (ref "U$2") (pin "P$15") (pinfunction "P$15_P$15") (pintype "bidirectional"))
    )
    (net (code "50") (name "Net-(IC4A-CO)") (class "Default")
      (node (ref "IC4") (pin "6") (pinfunction "CO_6") (pintype "output"))
      (node (ref "U$2") (pin "P$7") (pinfunction "P$7_P$7") (pintype "bidirectional"))
    )
    (net (code "51") (name "Net-(IC4A-DO)") (class "Default")
      (node (ref "IC4") (pin "10") (pinfunction "DO_10") (pintype "output"))
      (node (ref "U$2") (pin "P$8") (pinfunction "P$8_P$8") (pintype "bidirectional"))
    )
    (net (code "52") (name "Net-(IC4A-EO)") (class "Default")
      (node (ref "IC4") (pin "12") (pinfunction "EO_12") (pintype "output"))
      (node (ref "U$2") (pin "P$16") (pinfunction "P$16_P$16") (pintype "bidirectional"))
    )
    (net (code "53") (name "Net-(LED0-PadA)") (class "Default")
      (node (ref "LED0") (pin "A") (pinfunction "A_A") (pintype "passive"))
      (node (ref "R4") (pin "2") (pinfunction "2_2") (pintype "passive"))
    )
    (net (code "54") (name "Net-(LED1-PadA)") (class "Default")
      (node (ref "LED1") (pin "A") (pinfunction "A_A") (pintype "passive"))
      (node (ref "R3") (pin "2") (pinfunction "2_2") (pintype "passive"))
    )
    (net (code "55") (name "Net-(OK1-A)") (class "Default")
      (node (ref "D1") (pin "C") (pinfunction "C_C") (pintype "passive"))
      (node (ref "OK1") (pin "2") (pinfunction "A_2") (pintype "passive"))
      (node (ref "R5") (pin "2") (pinfunction "2_2") (pintype "passive"))
    )
    (net (code "56") (name "Net-(OK1-C)") (class "Default")
      (node (ref "D1") (pin "A") (pinfunction "A_A") (pintype "passive"))
      (node (ref "OK1") (pin "3") (pinfunction "C_3") (pintype "passive"))
      (node (ref "U$10") (pin "5") (pinfunction "5_5") (pintype "passive"))
    )
    (net (code "57") (name "Net-(OK2-A)") (class "Default")
      (node (ref "D2") (pin "C") (pinfunction "C_C") (pintype "passive"))
      (node (ref "OK2") (pin "2") (pinfunction "A_2") (pintype "passive"))
      (node (ref "R6") (pin "2") (pinfunction "2_2") (pintype "passive"))
    )
    (net (code "58") (name "Net-(OK2-C)") (class "Default")
      (node (ref "D2") (pin "A") (pinfunction "A_A") (pintype "passive"))
      (node (ref "OK2") (pin "3") (pinfunction "C_3") (pintype "passive"))
      (node (ref "U$8") (pin "5") (pinfunction "5_5") (pintype "passive"))
    )
    (net (code "59") (name "Net-(R5-Pad1)") (class "Default")
      (node (ref "R5") (pin "1") (pinfunction "1_1") (pintype "passive"))
      (node (ref "U$10") (pin "4") (pinfunction "4_4") (pintype "passive"))
    )
    (net (code "60") (name "Net-(R6-Pad1)") (class "Default")
      (node (ref "R6") (pin "1") (pinfunction "1_1") (pintype "passive"))
      (node (ref "U$8") (pin "4") (pinfunction "4_4") (pintype "passive"))
    )
    (net (code "61") (name "Net-(R7-Pad1)") (class "Default")
      (node (ref "R7") (pin "1") (pinfunction "1_1") (pintype "passive"))
      (node (ref "U$9") (pin "4") (pinfunction "4_4") (pintype "passive"))
    )
    (net (code "62") (name "Net-(R8-Pad1)") (class "Default")
      (node (ref "R8") (pin "1") (pinfunction "1_1") (pintype "passive"))
      (node (ref "U$9") (pin "5") (pinfunction "5_5") (pintype "passive"))
    )
    (net (code "63") (name "Net-(R9-Pad1)") (class "Default")
      (node (ref "R9") (pin "1") (pinfunction "1_1") (pintype "passive"))
      (node (ref "U$7") (pin "5") (pinfunction "5_5") (pintype "passive"))
    )
    (net (code "64") (name "Net-(R10-Pad1)") (class "Default")
      (node (ref "R10") (pin "1") (pinfunction "1_1") (pintype "passive"))
      (node (ref "U$7") (pin "4") (pinfunction "4_4") (pintype "passive"))
    )
    (net (code "65") (name "Net-(S1-S)") (class "Default")
      (node (ref "J1") (pin "2") (pinfunction "2_2") (pintype "passive"))
      (node (ref "J1") (pin "3") (pinfunction "3_3") (pintype "passive"))
      (node (ref "S1") (pin "3") (pinfunction "S_3") (pintype "passive"))
    )
    (net (code "66") (name "Net-(U$1-VO)") (class "Default")
      (node (ref "R13") (pin "S") (pinfunction "S_S") (pintype "passive"))
      (node (ref "R13") (pin "S1") (pinfunction "S_S1") (pintype "passive"))
      (node (ref "U$1") (pin "3") (pinfunction "VO_3") (pintype "bidirectional"))
    )
    (net (code "67") (name "PA0") (class "Default")
      (node (ref "IC1") (pin "2") (pinfunction "1D_2") (pintype "input"))
      (node (ref "U1") (pin "13") (pinfunction "DQ0_13") (pintype "bidirectional"))
      (node (ref "XIO") (pin "3") (pinfunction "3_3") (pintype "passive"))
    )
    (net (code "68") (name "PA1") (class "Default")
      (node (ref "IC1") (pin "3") (pinfunction "2D_3") (pintype "input"))
      (node (ref "U1") (pin "14") (pinfunction "DQ1_14") (pintype "bidirectional"))
      (node (ref "XIO") (pin "4") (pinfunction "4_4") (pintype "passive"))
    )
    (net (code "69") (name "PA2") (class "Default")
      (node (ref "IC1") (pin "4") (pinfunction "3D_4") (pintype "input"))
      (node (ref "U1") (pin "15") (pinfunction "DQ2_15") (pintype "bidirectional"))
      (node (ref "XIO") (pin "5") (pinfunction "5_5") (pintype "passive"))
    )
    (net (code "70") (name "PA3") (class "Default")
      (node (ref "IC1") (pin "5") (pinfunction "4D_5") (pintype "input"))
      (node (ref "U1") (pin "17") (pinfunction "DQ3_17") (pintype "bidirectional"))
      (node (ref "XIO") (pin "6") (pinfunction "6_6") (pintype "passive"))
    )
    (net (code "71") (name "PA4") (class "Default")
      (node (ref "IC1") (pin "6") (pinfunction "5D_6") (pintype "input"))
      (node (ref "U1") (pin "18") (pinfunction "DQ4_18") (pintype "bidirectional"))
      (node (ref "XIO") (pin "7") (pinfunction "7_7") (pintype "passive"))
    )
    (net (code "72") (name "PA5") (class "Default")
      (node (ref "IC1") (pin "7") (pinfunction "6D_7") (pintype "input"))
      (node (ref "U1") (pin "19") (pinfunction "DQ5_19") (pintype "bidirectional"))
      (node (ref "XIO") (pin "8") (pinfunction "8_8") (pintype "passive"))
    )
    (net (code "73") (name "PA6") (class "Default")
      (node (ref "IC1") (pin "8") (pinfunction "7D_8") (pintype "input"))
      (node (ref "U1") (pin "20") (pinfunction "DQ6_20") (pintype "bidirectional"))
      (node (ref "XIO") (pin "9") (pinfunction "9_9") (pintype "passive"))
    )
    (net (code "74") (name "PA7") (class "Default")
      (node (ref "IC1") (pin "9") (pinfunction "8D_9") (pintype "input"))
      (node (ref "U1") (pin "21") (pinfunction "DQ7_21") (pintype "bidirectional"))
      (node (ref "XIO") (pin "10") (pinfunction "10_10") (pintype "passive"))
    )
    (net (code "75") (name "PB0") (class "Default")
      (node (ref "JP1") (pin "7") (pinfunction "7_7") (pintype "passive"))
      (node (ref "XIO") (pin "34") (pinfunction "34_34") (pintype "passive"))
    )
    (net (code "76") (name "PB1") (class "Default")
      (node (ref "IC4") (pin "7") (pinfunction "CI_7") (pintype "input"))
      (node (ref "JP1") (pin "4") (pinfunction "4_4") (pintype "passive"))
      (node (ref "XIO") (pin "33") (pinfunction "33_33") (pintype "passive"))
    )
    (net (code "77") (name "PB2") (class "Default")
      (node (ref "IC4") (pin "9") (pinfunction "DI_9") (pintype "input"))
      (node (ref "JP1") (pin "6") (pinfunction "6_6") (pintype "passive"))
      (node (ref "XIO") (pin "32") (pinfunction "32_32") (pintype "passive"))
    )
    (net (code "78") (name "PB3") (class "Default")
      (node (ref "JP1") (pin "5") (pinfunction "5_5") (pintype "passive"))
      (node (ref "XIO") (pin "31") (pinfunction "31_31") (pintype "passive"))
    )
    (net (code "79") (name "PB4") (class "Default")
      (node (ref "JP6") (pin "8") (pinfunction "8_8") (pintype "passive"))
    )
    (net (code "80") (name "PB5") (class "Default")
      (node (ref "JP6") (pin "7") (pinfunction "7_7") (pintype "passive"))
    )
    (net (code "81") (name "PB6") (class "Default")
      (node (ref "JP6") (pin "6") (pinfunction "6_6") (pintype "passive"))
    )
    (net (code "82") (name "PB7") (class "Default")
      (node (ref "JP6") (pin "5") (pinfunction "5_5") (pintype "passive"))
    )
    (net (code "83") (name "PC0") (class "Default")
      (node (ref "U1") (pin "27") (pinfunction "A8_27") (pintype "input"))
      (node (ref "XIO") (pin "18") (pinfunction "18_18") (pintype "passive"))
    )
    (net (code "84") (name "PC1") (class "Default")
      (node (ref "U1") (pin "26") (pinfunction "A9_26") (pintype "input"))
      (node (ref "XIO") (pin "17") (pinfunction "17_17") (pintype "passive"))
    )
    (net (code "85") (name "PC2") (class "Default")
      (node (ref "U1") (pin "23") (pinfunction "A10_23") (pintype "input"))
      (node (ref "XIO") (pin "16") (pinfunction "16_16") (pintype "passive"))
    )
    (net (code "86") (name "PC3") (class "Default")
      (node (ref "U1") (pin "25") (pinfunction "A11_25") (pintype "input"))
      (node (ref "XIO") (pin "15") (pinfunction "15_15") (pintype "passive"))
    )
    (net (code "87") (name "PC4") (class "Default")
      (node (ref "U1") (pin "4") (pinfunction "A12_4") (pintype "input"))
      (node (ref "XIO") (pin "14") (pinfunction "14_14") (pintype "passive"))
    )
    (net (code "88") (name "PC5") (class "Default")
      (node (ref "U1") (pin "28") (pinfunction "A13_28") (pintype "input"))
      (node (ref "XIO") (pin "13") (pinfunction "13_13") (pintype "passive"))
    )
    (net (code "89") (name "PC6") (class "Default")
      (node (ref "U1") (pin "3") (pinfunction "A14_3") (pintype "input"))
      (node (ref "XIO") (pin "12") (pinfunction "12_12") (pintype "passive"))
    )
    (net (code "90") (name "PC7") (class "Default")
      (node (ref "U1") (pin "31") (pinfunction "A15_31") (pintype "input"))
      (node (ref "XIO") (pin "11") (pinfunction "11_11") (pintype "passive"))
    )
    (net (code "91") (name "PD0") (class "Default")
      (node (ref "COMMUNICATION") (pin "1") (pinfunction "1_1") (pintype "passive"))
    )
    (net (code "92") (name "PD1") (class "Default")
      (node (ref "COMMUNICATION") (pin "2") (pinfunction "2_2") (pintype "passive"))
    )
    (net (code "93") (name "PD7") (class "Default")
      (node (ref "IC4") (pin "11") (pinfunction "EI_11") (pintype "input"))
      (node (ref "XIO") (pin "19") (pinfunction "19_19") (pintype "passive"))
    )
    (net (code "94") (name "PE0") (class "Default")
      (node (ref "PWML") (pin "1") (pinfunction "1_1") (pintype "passive"))
    )
    (net (code "95") (name "PE1") (class "Default")
      (node (ref "PWML") (pin "2") (pinfunction "2_2") (pintype "passive"))
    )
    (net (code "96") (name "PE3") (class "Default")
      (node (ref "PWML") (pin "6") (pinfunction "6_6") (pintype "passive"))
    )
    (net (code "97") (name "PE4") (class "Default")
      (node (ref "PWML") (pin "3") (pinfunction "3_3") (pintype "passive"))
      (node (ref "R3") (pin "1") (pinfunction "1_1") (pintype "passive"))
    )
    (net (code "98") (name "PE5") (class "Default")
      (node (ref "PWML") (pin "4") (pinfunction "4_4") (pintype "passive"))
      (node (ref "R4") (pin "1") (pinfunction "1_1") (pintype "passive"))
    )
    (net (code "99") (name "PG0") (class "Default")
      (node (ref "U1") (pin "29") (pinfunction "WE_29") (pintype "input"))
      (node (ref "XIO") (pin "22") (pinfunction "22_22") (pintype "passive"))
    )
    (net (code "100") (name "PG1") (class "Default")
      (node (ref "U1") (pin "24") (pinfunction "OE_24") (pintype "input"))
      (node (ref "XIO") (pin "21") (pinfunction "21_21") (pintype "passive"))
    )
    (net (code "101") (name "PG2") (class "Default")
      (node (ref "IC1") (pin "11") (pinfunction "C_11") (pintype "input"))
      (node (ref "XIO") (pin "20") (pinfunction "20_20") (pintype "passive"))
    )
    (net (code "102") (name "PG5") (class "Default")
      (node (ref "PWML") (pin "5") (pinfunction "5_5") (pintype "passive"))
    )
    (net (code "103") (name "PH3") (class "Default")
      (node (ref "PWML") (pin "7") (pinfunction "7_7") (pintype "passive"))
    )
    (net (code "104") (name "PH4") (class "Default")
      (node (ref "PWML") (pin "8") (pinfunction "8_8") (pintype "passive"))
    )
    (net (code "105") (name "PH5") (class "Default")
      (node (ref "JP6") (pin "10") (pinfunction "10_10") (pintype "passive"))
    )
    (net (code "106") (name "PH6") (class "Default")
      (node (ref "JP6") (pin "9") (pinfunction "9_9") (pintype "passive"))
    )
    (net (code "107") (name "PL0") (class "Default")
      (node (ref "IC3") (pin "9") (pinfunction "QH_9") (pintype "output"))
      (node (ref "XIO") (pin "30") (pinfunction "30_30") (pintype "passive"))
    )
    (net (code "108") (name "PL1") (class "Default")
      (node (ref "IC2") (pin "1") (pinfunction "SH/~{LD}_1") (pintype "input"))
      (node (ref "IC3") (pin "1") (pinfunction "SH/~{LD}_1") (pintype "input"))
      (node (ref "XIO") (pin "29") (pinfunction "29_29") (pintype "passive"))
    )
    (net (code "109") (name "PL2") (class "Default")
      (node (ref "IC2") (pin "2") (pinfunction "CLK_2") (pintype "input"))
      (node (ref "IC3") (pin "2") (pinfunction "CLK_2") (pintype "input"))
      (node (ref "XIO") (pin "28") (pinfunction "28_28") (pintype "passive"))
    )
    (net (code "110") (name "PL3") (class "Default")
      (node (ref "U$1") (pin "4") (pinfunction "RS_4") (pintype "input"))
      (node (ref "XIO") (pin "27") (pinfunction "27_27") (pintype "passive"))
    )
    (net (code "111") (name "PL4") (class "Default")
      (node (ref "U$1") (pin "6") (pinfunction "E_6") (pintype "input"))
      (node (ref "XIO") (pin "26") (pinfunction "26_26") (pintype "passive"))
    )
    (net (code "112") (name "PL5") (class "Default")
      (node (ref "IC4") (pin "3") (pinfunction "AI_3") (pintype "input"))
      (node (ref "XIO") (pin "25") (pinfunction "25_25") (pintype "passive"))
    )
    (net (code "113") (name "PL6") (class "Default")
      (node (ref "U1") (pin "2") (pinfunction "A16_2") (pintype "input"))
      (node (ref "XIO") (pin "24") (pinfunction "24_24") (pintype "passive"))
    )
    (net (code "114") (name "PL7") (class "Default")
      (node (ref "IC4") (pin "5") (pinfunction "BI_5") (pintype "input"))
      (node (ref "XIO") (pin "23") (pinfunction "23_23") (pintype "passive"))
    )
    (net (code "115") (name "RESET") (class "Default")
      (node (ref "POWER") (pin "3") (pinfunction "3_3") (pintype "passive"))
    )
    (net (code "116") (name "RXD1") (class "Default")
      (node (ref "COMMUNICATION") (pin "3") (pinfunction "3_3") (pintype "passive"))
      (node (ref "OK1") (pin "6") (pinfunction "VO_6") (pintype "passive"))
      (node (ref "R12") (pin "1") (pinfunction "1_1") (pintype "passive"))
    )
    (net (code "117") (name "RXD2") (class "Default")
      (node (ref "COMMUNICATION") (pin "5") (pinfunction "5_5") (pintype "passive"))
      (node (ref "OK2") (pin "6") (pinfunction "VO_6") (pintype "passive"))
      (node (ref "R11") (pin "1") (pinfunction "1_1") (pintype "passive"))
    )
    (net (code "118") (name "RXD3") (class "Default")
      (node (ref "COMMUNICATION") (pin "7") (pinfunction "7_7") (pintype "passive"))
    )
    (net (code "119") (name "SCL") (class "Default")
      (node (ref "JP6") (pin "1") (pinfunction "1_1") (pintype "passive"))
    )
    (net (code "120") (name "TXD1") (class "Default")
      (node (ref "COMMUNICATION") (pin "4") (pinfunction "4_4") (pintype "passive"))
      (node (ref "R8") (pin "2") (pinfunction "2_2") (pintype "passive"))
    )
    (net (code "121") (name "TXD2") (class "Default")
      (node (ref "COMMUNICATION") (pin "6") (pinfunction "6_6") (pintype "passive"))
      (node (ref "R9") (pin "2") (pinfunction "2_2") (pintype "passive"))
    )
    (net (code "122") (name "TXD3") (class "Default")
      (node (ref "COMMUNICATION") (pin "8") (pinfunction "8_8") (pintype "passive"))
    )
    (net (code "123") (name "VDD") (class "Default")
      (node (ref "IC4") (pin "16") (pinfunction "VDD_16") (pintype "power_in"))
    )
    (net (code "124") (name "VIN") (class "Default")
      (node (ref "POWER") (pin "8") (pinfunction "8_8") (pintype "passive"))
      (node (ref "S1") (pin "2") (pinfunction "P_2") (pintype "passive"))
    )
    (net (code "125") (name "unconnected-(IC2A-~{QH}-Pad7)") (class "Default")
      (node (ref "IC2") (pin "7") (pinfunction "~{QH}_7") (pintype "output"))
    )
    (net (code "126") (name "unconnected-(IC3A-~{QH}-Pad7)") (class "Default")
      (node (ref "IC3") (pin "7") (pinfunction "~{QH}_7") (pintype "output"))
    )
    (net (code "127") (name "unconnected-(IC4A-FI-Pad14)") (class "Default")
      (node (ref "IC4") (pin "14") (pinfunction "FI_14") (pintype "input"))
    )
    (net (code "128") (name "unconnected-(IC4A-FO-Pad15)") (class "Default")
      (node (ref "IC4") (pin "15") (pinfunction "FO_15") (pintype "output"))
    )
    (net (code "129") (name "unconnected-(IC4A-MODE-Pad13)") (class "Default")
      (node (ref "IC4") (pin "13") (pinfunction "MODE_13") (pintype "input"))
    )
    (net (code "130") (name "unconnected-(JP1-Pad2)") (class "Default")
      (node (ref "JP1") (pin "2") (pinfunction "2_2") (pintype "passive"))
    )
    (net (code "131") (name "unconnected-(OK1-VE-Pad7)") (class "Default")
      (node (ref "OK1") (pin "7") (pinfunction "VE_7") (pintype "passive"))
    )
    (net (code "132") (name "unconnected-(OK2-VE-Pad7)") (class "Default")
      (node (ref "OK2") (pin "7") (pinfunction "VE_7") (pintype "passive"))
    )
    (net (code "133") (name "unconnected-(POWER-Pad1)") (class "Default")
      (node (ref "POWER") (pin "1") (pinfunction "1_1") (pintype "passive"))
    )
    (net (code "134") (name "unconnected-(POWER-Pad2)") (class "Default")
      (node (ref "POWER") (pin "2") (pinfunction "2_2") (pintype "passive"))
    )
    (net (code "135") (name "unconnected-(S1-O-Pad1)") (class "Default")
      (node (ref "S1") (pin "1") (pinfunction "O_1") (pintype "passive"))
    )
    (net (code "136") (name "unconnected-(U$1-DB0-Pad7)") (class "Default")
      (node (ref "U$1") (pin "7") (pinfunction "DB0_7") (pintype "bidirectional"))
    )
    (net (code "137") (name "unconnected-(U$1-DB1-Pad8)") (class "Default")
      (node (ref "U$1") (pin "8") (pinfunction "DB1_8") (pintype "bidirectional"))
    )
    (net (code "138") (name "unconnected-(U$1-DB2-Pad9)") (class "Default")
      (node (ref "U$1") (pin "9") (pinfunction "DB2_9") (pintype "bidirectional"))
    )
    (net (code "139") (name "unconnected-(U$1-DB3-Pad10)") (class "Default")
      (node (ref "U$1") (pin "10") (pinfunction "DB3_10") (pintype "bidirectional"))
    )
    (net (code "140") (name "unconnected-(U$2-PadP$3)") (class "Default")
      (node (ref "U$2") (pin "P$3") (pinfunction "P$3_P$3") (pintype "bidirectional"))
    )
    (net (code "141") (name "unconnected-(U$2-PadP$5)") (class "Default")
      (node (ref "U$2") (pin "P$5") (pinfunction "P$5_P$5") (pintype "bidirectional"))
    )
    (net (code "142") (name "unconnected-(U$2-PadP$6)") (class "Default")
      (node (ref "U$2") (pin "P$6") (pinfunction "P$6_P$6") (pintype "bidirectional"))
    )
    (net (code "143") (name "unconnected-(U$2-PadP$9)") (class "Default")
      (node (ref "U$2") (pin "P$9") (pinfunction "P$9_P$9") (pintype "bidirectional"))
    )
    (net (code "144") (name "unconnected-(U$2-PadP$10)") (class "Default")
      (node (ref "U$2") (pin "P$10") (pinfunction "P$10_P$10") (pintype "bidirectional"))
    )
    (net (code "145") (name "unconnected-(U$2-PadP$11)") (class "Default")
      (node (ref "U$2") (pin "P$11") (pinfunction "P$11_P$11") (pintype "bidirectional"))
    )
    (net (code "146") (name "unconnected-(U$2-PadP$12)") (class "Default")
      (node (ref "U$2") (pin "P$12") (pinfunction "P$12_P$12") (pintype "bidirectional"))
    )
    (net (code "147") (name "unconnected-(U$2-PadP$13)") (class "Default")
      (node (ref "U$2") (pin "P$13") (pinfunction "P$13_P$13") (pintype "bidirectional"))
    )
    (net (code "148") (name "unconnected-(U$2-PadP$14)") (class "Default")
      (node (ref "U$2") (pin "P$14") (pinfunction "P$14_P$14") (pintype "bidirectional"))
    )
    (net (code "149") (name "unconnected-(U$2-PadP$17)") (class "Default")
      (node (ref "U$2") (pin "P$17") (pinfunction "P$17_P$17") (pintype "bidirectional"))
    )
    (net (code "150") (name "unconnected-(U$2-PadP$18)") (class "Default")
      (node (ref "U$2") (pin "P$18") (pinfunction "P$18_P$18") (pintype "bidirectional"))
    )
    (net (code "151") (name "unconnected-(U$2-PadP$19)") (class "Default")
      (node (ref "U$2") (pin "P$19") (pinfunction "P$19_P$19") (pintype "bidirectional"))
    )
    (net (code "152") (name "unconnected-(U$2-PadP$20)") (class "Default")
      (node (ref "U$2") (pin "P$20") (pinfunction "P$20_P$20") (pintype "bidirectional"))
    )
    (net (code "153") (name "unconnected-(U$7-Pad1)") (class "Default")
      (node (ref "U$7") (pin "1") (pinfunction "1_1") (pintype "passive"))
    )
    (net (code "154") (name "unconnected-(U$7-Pad3)") (class "Default")
      (node (ref "U$7") (pin "3") (pinfunction "3_3") (pintype "passive"))
    )
    (net (code "155") (name "unconnected-(U$8-Pad1)") (class "Default")
      (node (ref "U$8") (pin "1") (pinfunction "1_1") (pintype "passive"))
    )
    (net (code "156") (name "unconnected-(U$8-Pad2)") (class "Default")
      (node (ref "U$8") (pin "2") (pinfunction "2_2") (pintype "passive"))
    )
    (net (code "157") (name "unconnected-(U$8-Pad3)") (class "Default")
      (node (ref "U$8") (pin "3") (pinfunction "3_3") (pintype "passive"))
    )
    (net (code "158") (name "unconnected-(U$9-Pad1)") (class "Default")
      (node (ref "U$9") (pin "1") (pinfunction "1_1") (pintype "passive"))
    )
    (net (code "159") (name "unconnected-(U$9-Pad3)") (class "Default")
      (node (ref "U$9") (pin "3") (pinfunction "3_3") (pintype "passive"))
    )
    (net (code "160") (name "unconnected-(U$10-Pad1)") (class "Default")
      (node (ref "U$10") (pin "1") (pinfunction "1_1") (pintype "passive"))
    )
    (net (code "161") (name "unconnected-(U$10-Pad2)") (class "Default")
      (node (ref "U$10") (pin "2") (pinfunction "2_2") (pintype "passive"))
    )
    (net (code "162") (name "unconnected-(U$10-Pad3)") (class "Default")
      (node (ref "U$10") (pin "3") (pinfunction "3_3") (pintype "passive"))
    )
    (net (code "163") (name "unconnected-(U1-NC-Pad1)") (class "Default")
      (node (ref "U1") (pin "1") (pinfunction "NC_1") (pintype "no_connect"))
    )
    (net (code "164") (name "unconnected-(XIO-Pad1)") (class "Default")
      (node (ref "XIO") (pin "1") (pinfunction "1_1") (pintype "passive"))
    )
    (net (code "165") (name "unconnected-(XIO-Pad2)") (class "Default")
      (node (ref "XIO") (pin "2") (pinfunction "2_2") (pintype "passive"))
    )
  )
)
